# simple_module_tester.net
KiCad netlist of a schematic drawn in EAGLE
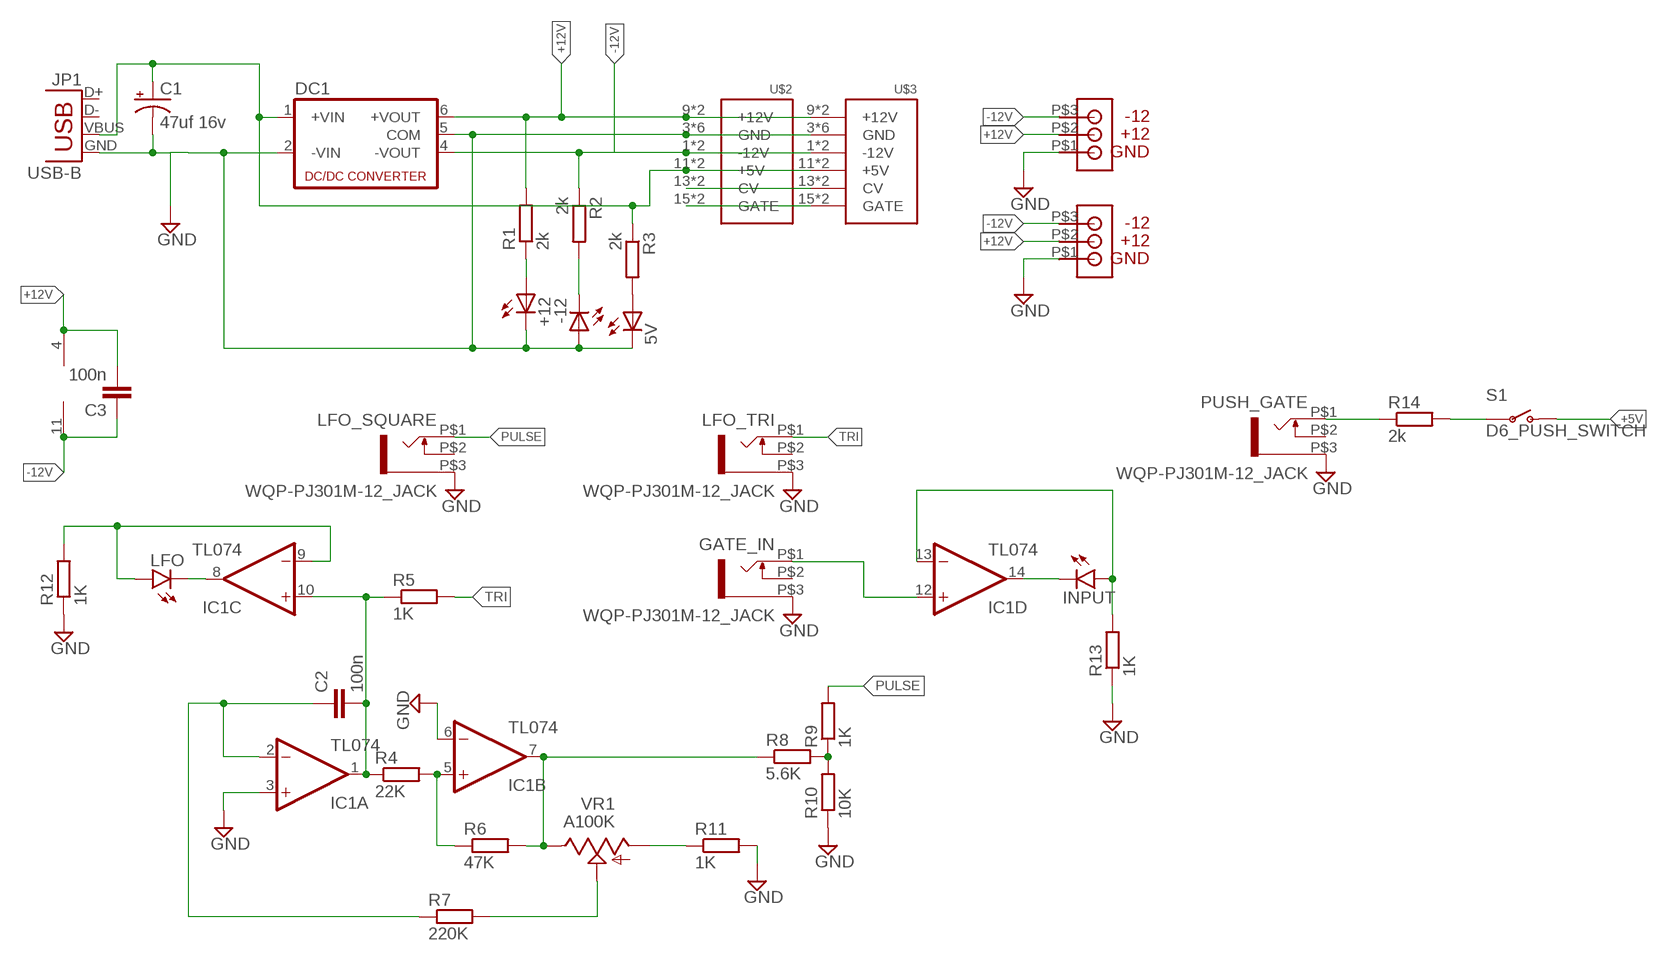
[diagram p0: schematic, sheet 1]

(export (version "E")
  (design (tool "Eeschema 10.0.6"))
  (components
    (comp (ref "+12")
      (value "LED3MM")
      (footprint "eagle-import:LED3MM")
      (libsource (lib "eagle-import") (part "TomW_LED3MM"))
    )
    (comp (ref "-12")
      (value "LED3MM")
      (footprint "eagle-import:LED3MM")
      (libsource (lib "eagle-import") (part "TomW_LED3MM"))
    )
    (comp (ref "5V")
      (value "LED3MM")
      (footprint "eagle-import:LED3MM")
      (libsource (lib "eagle-import") (part "TomW_LED3MM"))
    )
    (comp (ref "C1")
      (value "47uf 16v")
      (footprint "eagle-import:050_020")
      (libsource (lib "eagle-import") (part "050"))
    )
    (comp (ref "C2")
      (value "100n")
      (footprint "eagle-import:AXIAL-5MM")
      (libsource (lib "eagle-import") (part "CAP_"))
    )
    (comp (ref "C3")
      (value "100n")
      (footprint "eagle-import:AXIAL-5MM")
      (libsource (lib "eagle-import") (part "CAP_"))
    )
    (comp (ref "DC1")
      (value "NMA")
      (footprint "eagle-import:NMA")
      (fields (field (name "MF") "C & D TECHNOLOGIES, INC") (field (name "MPN") "NMA0515SC"))
      (libsource (lib "eagle-import") (part "NMA"))
    )
    (comp (ref "GATE_IN")
      (value "WQP-PJ301M-12_JACK")
      (footprint "eagle-import:WQP-PJ301M-12_JACK")
      (libsource (lib "eagle-import") (part "WQP-PJ301M-12_JACK"))
    )
    (comp (ref "IC1")
      (value "TL074")
      (footprint "eagle-import:DIL14")
      (libsource (lib "eagle-import") (part "TL074_"))
    )
    (comp (ref "INPUT")
      (value "LED5MM")
      (footprint "eagle-import:LED5MM")
      (libsource (lib "eagle-import") (part "LED5MM"))
    )
    (comp (ref "JP1")
      (value "USB-B")
      (footprint "eagle-import:USB-B-PTH")
      (libsource (lib "eagle-import") (part "USBPTH"))
    )
    (comp (ref "LFO")
      (value "LED5MM")
      (footprint "eagle-import:LED5MM")
      (libsource (lib "eagle-import") (part "LED5MM"))
    )
    (comp (ref "LFO_SQUARE")
      (value "WQP-PJ301M-12_JACK")
      (footprint "eagle-import:WQP-PJ301M-12_JACK")
      (libsource (lib "eagle-import") (part "WQP-PJ301M-12_JACK"))
    )
    (comp (ref "LFO_TRI")
      (value "WQP-PJ301M-12_JACK")
      (footprint "eagle-import:WQP-PJ301M-12_JACK")
      (libsource (lib "eagle-import") (part "WQP-PJ301M-12_JACK"))
    )
    (comp (ref "PUSH_GATE")
      (value "WQP-PJ301M-12_JACK")
      (footprint "eagle-import:WQP-PJ301M-12_JACK")
      (libsource (lib "eagle-import") (part "WQP-PJ301M-12_JACK"))
    )
    (comp (ref "R1")
      (value "2k")
      (footprint "eagle-import:7MM_RESISTOR")
      (libsource (lib "eagle-import") (part "RESISTOR7MM"))
    )
    (comp (ref "R2")
      (value "2k")
      (footprint "eagle-import:7MM_RESISTOR")
      (libsource (lib "eagle-import") (part "RESISTOR7MM"))
    )
    (comp (ref "R3")
      (value "2k")
      (footprint "eagle-import:7MM_RESISTOR")
      (libsource (lib "eagle-import") (part "RESISTOR7MM"))
    )
    (comp (ref "R4")
      (value "22K")
      (footprint "eagle-import:7MM_RESISTOR")
      (libsource (lib "eagle-import") (part "RESISTOR7MM"))
    )
    (comp (ref "R5")
      (value "1K")
      (footprint "eagle-import:7MM_RESISTOR")
      (libsource (lib "eagle-import") (part "RESISTOR7MM"))
    )
    (comp (ref "R6")
      (value "47K")
      (footprint "eagle-import:7MM_RESISTOR")
      (libsource (lib "eagle-import") (part "RESISTOR7MM"))
    )
    (comp (ref "R7")
      (value "220K")
      (footprint "eagle-import:7MM_RESISTOR")
      (libsource (lib "eagle-import") (part "RESISTOR7MM"))
    )
    (comp (ref "R8")
      (value "5.6K")
      (footprint "eagle-import:7MM_RESISTOR")
      (libsource (lib "eagle-import") (part "RESISTOR7MM"))
    )
    (comp (ref "R9")
      (value "1K")
      (footprint "eagle-import:7MM_RESISTOR")
      (libsource (lib "eagle-import") (part "RESISTOR7MM"))
    )
    (comp (ref "R10")
      (value "10K")
      (footprint "eagle-import:7MM_RESISTOR")
      (libsource (lib "eagle-import") (part "RESISTOR7MM"))
    )
    (comp (ref "R11")
      (value "1K")
      (footprint "eagle-import:7MM_RESISTOR")
      (libsource (lib "eagle-import") (part "RESISTOR7MM"))
    )
    (comp (ref "R12")
      (value "1K")
      (footprint "eagle-import:7MM_RESISTOR")
      (libsource (lib "eagle-import") (part "RESISTOR7MM"))
    )
    (comp (ref "R13")
      (value "1K")
      (footprint "eagle-import:7MM_RESISTOR")
      (libsource (lib "eagle-import") (part "RESISTOR7MM"))
    )
    (comp (ref "R14")
      (value "2k")
      (footprint "eagle-import:7MM_RESISTOR")
      (libsource (lib "eagle-import") (part "RESISTOR7MM"))
    )
    (comp (ref "S1")
      (value "D6_PUSH_SWITCH")
      (footprint "eagle-import:D6_PUSH_SWITCH")
      (libsource (lib "eagle-import") (part "D6_PUSH_SWITCH"))
    )
    (comp (ref "U$1")
      (value "TILE_POWER_WIDE")
      (footprint "eagle-import:THREEPAD_WIDE")
      (libsource (lib "eagle-import") (part "TILE_POWER_WIDE"))
    )
    (comp (ref "U$2")
      (value "POWER")
      (footprint "eagle-import:POWER_16")
      (libsource (lib "eagle-import") (part "POWER"))
    )
    (comp (ref "U$3")
      (value "POWER")
      (footprint "eagle-import:POWER_16")
      (libsource (lib "eagle-import") (part "POWER"))
    )
    (comp (ref "U$4")
      (value "TILE_POWER_WIDE")
      (footprint "eagle-import:THREEPAD_WIDE")
      (libsource (lib "eagle-import") (part "TILE_POWER_WIDE"))
    )
    (comp (ref "VR1")
      (value "A100K")
      (footprint "eagle-import:9MM_SNAP-IN_POT")
      (libsource (lib "eagle-import") (part "9MM_SNAP-IN_POT_"))
    )
  )
  (nets
    (net (code "1") (name "+5V") (class "Default")
      (node (ref "C1") (pin "+") (pinfunction "+_+") (pintype "passive"))
      (node (ref "DC1") (pin "1") (pinfunction "+VIN_1") (pintype "passive"))
      (node (ref "JP1") (pin "VBUS") (pinfunction "VBUS_VBUS") (pintype "bidirectional"))
      (node (ref "R3") (pin "1") (pinfunction "1_1") (pintype "passive"))
      (node (ref "S1") (pin "P$1") (pinfunction "O_P$1") (pintype "passive"))
      (node (ref "S1") (pin "P$2") (pinfunction "O_P$2") (pintype "passive"))
      (node (ref "U$2") (pin "11") (pinfunction "+5V_11") (pintype "bidirectional"))
      (node (ref "U$2") (pin "12") (pinfunction "+5V_12") (pintype "bidirectional"))
      (node (ref "U$3") (pin "11") (pinfunction "+5V_11") (pintype "bidirectional"))
      (node (ref "U$3") (pin "12") (pinfunction "+5V_12") (pintype "bidirectional"))
    )
    (net (code "2") (name "+12V") (class "Default")
      (node (ref "C3") (pin "P$2") (pinfunction "2_P$2") (pintype "passive"))
      (node (ref "DC1") (pin "6") (pinfunction "+VOUT_6") (pintype "passive"))
      (node (ref "IC1") (pin "4") (pinfunction "V+_4") (pintype "power_in"))
      (node (ref "R1") (pin "2") (pinfunction "2_2") (pintype "passive"))
      (node (ref "U$1") (pin "P$2") (pinfunction "P$2_P$2") (pintype "bidirectional"))
      (node (ref "U$2") (pin "10") (pinfunction "+12V_10") (pintype "bidirectional"))
      (node (ref "U$2") (pin "9") (pinfunction "+12V_9") (pintype "bidirectional"))
      (node (ref "U$3") (pin "10") (pinfunction "+12V_10") (pintype "bidirectional"))
      (node (ref "U$3") (pin "9") (pinfunction "+12V_9") (pintype "bidirectional"))
      (node (ref "U$4") (pin "P$2") (pinfunction "P$2_P$2") (pintype "bidirectional"))
    )
    (net (code "3") (name "-12V") (class "Default")
      (node (ref "C3") (pin "P$1") (pinfunction "1_P$1") (pintype "passive"))
      (node (ref "DC1") (pin "4") (pinfunction "-VOUT_4") (pintype "passive"))
      (node (ref "IC1") (pin "11") (pinfunction "V-_11") (pintype "power_in"))
      (node (ref "R2") (pin "1") (pinfunction "1_1") (pintype "passive"))
      (node (ref "U$1") (pin "P$3") (pinfunction "P$3_P$3") (pintype "bidirectional"))
      (node (ref "U$2") (pin "1") (pinfunction "-12V_1") (pintype "bidirectional"))
      (node (ref "U$2") (pin "2") (pinfunction "-12V_2") (pintype "bidirectional"))
      (node (ref "U$3") (pin "1") (pinfunction "-12V_1") (pintype "bidirectional"))
      (node (ref "U$3") (pin "2") (pinfunction "-12V_2") (pintype "bidirectional"))
      (node (ref "U$4") (pin "P$3") (pinfunction "P$3_P$3") (pintype "bidirectional"))
    )
    (net (code "4") (name "GND") (class "Default")
      (node (ref "+12") (pin "K") (pinfunction "C_K") (pintype "passive"))
      (node (ref "-12") (pin "A") (pinfunction "A_A") (pintype "passive"))
      (node (ref "5V") (pin "K") (pinfunction "C_K") (pintype "passive"))
      (node (ref "C1") (pin "-") (pinfunction "-_-") (pintype "passive"))
      (node (ref "DC1") (pin "2") (pinfunction "-VIN_2") (pintype "passive"))
      (node (ref "DC1") (pin "5") (pinfunction "COM_5") (pintype "passive"))
      (node (ref "GATE_IN") (pin "P$3") (pinfunction "1_P$3") (pintype "passive"))
      (node (ref "IC1") (pin "3") (pinfunction "+IN_3") (pintype "input"))
      (node (ref "IC1") (pin "6") (pinfunction "-IN_6") (pintype "input"))
      (node (ref "JP1") (pin "GND") (pinfunction "GND_GND") (pintype "bidirectional"))
      (node (ref "LFO_SQUARE") (pin "P$3") (pinfunction "1_P$3") (pintype "passive"))
      (node (ref "LFO_TRI") (pin "P$3") (pinfunction "1_P$3") (pintype "passive"))
      (node (ref "PUSH_GATE") (pin "P$3") (pinfunction "1_P$3") (pintype "passive"))
      (node (ref "R10") (pin "1") (pinfunction "1_1") (pintype "passive"))
      (node (ref "R11") (pin "2") (pinfunction "2_2") (pintype "passive"))
      (node (ref "R12") (pin "1") (pinfunction "1_1") (pintype "passive"))
      (node (ref "R13") (pin "1") (pinfunction "1_1") (pintype "passive"))
      (node (ref "U$1") (pin "P$1") (pinfunction "P$1_P$1") (pintype "bidirectional"))
      (node (ref "U$2") (pin "3") (pinfunction "GND_3") (pintype "bidirectional"))
      (node (ref "U$2") (pin "4") (pinfunction "GND_4") (pintype "bidirectional"))
      (node (ref "U$2") (pin "5") (pinfunction "GND_5") (pintype "bidirectional"))
      (node (ref "U$2") (pin "6") (pinfunction "GND_6") (pintype "bidirectional"))
      (node (ref "U$2") (pin "7") (pinfunction "GND_7") (pintype "bidirectional"))
      (node (ref "U$2") (pin "8") (pinfunction "GND_8") (pintype "bidirectional"))
      (node (ref "U$3") (pin "3") (pinfunction "GND_3") (pintype "bidirectional"))
      (node (ref "U$3") (pin "4") (pinfunction "GND_4") (pintype "bidirectional"))
      (node (ref "U$3") (pin "5") (pinfunction "GND_5") (pintype "bidirectional"))
      (node (ref "U$3") (pin "6") (pinfunction "GND_6") (pintype "bidirectional"))
      (node (ref "U$3") (pin "7") (pinfunction "GND_7") (pintype "bidirectional"))
      (node (ref "U$3") (pin "8") (pinfunction "GND_8") (pintype "bidirectional"))
      (node (ref "U$4") (pin "P$1") (pinfunction "P$1_P$1") (pintype "bidirectional"))
    )
    (net (code "5") (name "Net-(+12-PadA)") (class "Default")
      (node (ref "+12") (pin "A") (pinfunction "A_A") (pintype "passive"))
      (node (ref "R1") (pin "1") (pinfunction "1_1") (pintype "passive"))
    )
    (net (code "6") (name "Net-(-12-C)") (class "Default")
      (node (ref "-12") (pin "K") (pinfunction "C_K") (pintype "passive"))
      (node (ref "R2") (pin "2") (pinfunction "2_2") (pintype "passive"))
    )
    (net (code "7") (name "Net-(5V-PadA)") (class "Default")
      (node (ref "5V") (pin "A") (pinfunction "A_A") (pintype "passive"))
      (node (ref "R3") (pin "2") (pinfunction "2_2") (pintype "passive"))
    )
    (net (code "8") (name "Net-(C2-1)") (class "Default")
      (node (ref "C2") (pin "P$1") (pinfunction "1_P$1") (pintype "passive"))
      (node (ref "IC1") (pin "2") (pinfunction "-IN_2") (pintype "input"))
      (node (ref "R7") (pin "1") (pinfunction "1_1") (pintype "passive"))
    )
    (net (code "9") (name "Net-(C2-2)") (class "Default")
      (node (ref "C2") (pin "P$2") (pinfunction "2_P$2") (pintype "passive"))
      (node (ref "IC1") (pin "1") (pinfunction "OUT_1") (pintype "output"))
      (node (ref "IC1") (pin "10") (pinfunction "+IN_10") (pintype "input"))
      (node (ref "R4") (pin "1") (pinfunction "1_1") (pintype "passive"))
      (node (ref "R5") (pin "1") (pinfunction "1_1") (pintype "passive"))
    )
    (net (code "10") (name "Net-(GATE_IN-2)") (class "Default")
      (node (ref "GATE_IN") (pin "P$1") (pinfunction "2_P$1") (pintype "passive"))
      (node (ref "IC1") (pin "12") (pinfunction "+IN_12") (pintype "input"))
    )
    (net (code "11") (name "Net-(IC1B-+IN)") (class "Default")
      (node (ref "IC1") (pin "5") (pinfunction "+IN_5") (pintype "input"))
      (node (ref "R4") (pin "2") (pinfunction "2_2") (pintype "passive"))
      (node (ref "R6") (pin "1") (pinfunction "1_1") (pintype "passive"))
    )
    (net (code "12") (name "Net-(IC1B-OUT)") (class "Default")
      (node (ref "IC1") (pin "7") (pinfunction "OUT_7") (pintype "output"))
      (node (ref "R6") (pin "2") (pinfunction "2_2") (pintype "passive"))
      (node (ref "R8") (pin "1") (pinfunction "1_1") (pintype "passive"))
      (node (ref "VR1") (pin "3") (pinfunction "E_3") (pintype "passive"))
    )
    (net (code "13") (name "Net-(IC1C--IN)") (class "Default")
      (node (ref "IC1") (pin "9") (pinfunction "-IN_9") (pintype "input"))
      (node (ref "LFO") (pin "A") (pinfunction "A_A") (pintype "passive"))
      (node (ref "R12") (pin "2") (pinfunction "2_2") (pintype "passive"))
    )
    (net (code "14") (name "Net-(IC1C-OUT)") (class "Default")
      (node (ref "IC1") (pin "8") (pinfunction "OUT_8") (pintype "output"))
      (node (ref "LFO") (pin "K") (pinfunction "C_K") (pintype "passive"))
    )
    (net (code "15") (name "Net-(IC1D--IN)") (class "Default")
      (node (ref "IC1") (pin "13") (pinfunction "-IN_13") (pintype "input"))
      (node (ref "INPUT") (pin "A") (pinfunction "A_A") (pintype "passive"))
      (node (ref "R13") (pin "2") (pinfunction "2_2") (pintype "passive"))
    )
    (net (code "16") (name "Net-(IC1D-OUT)") (class "Default")
      (node (ref "IC1") (pin "14") (pinfunction "OUT_14") (pintype "output"))
      (node (ref "INPUT") (pin "K") (pinfunction "C_K") (pintype "passive"))
    )
    (net (code "17") (name "Net-(PUSH_GATE-2)") (class "Default")
      (node (ref "PUSH_GATE") (pin "P$1") (pinfunction "2_P$1") (pintype "passive"))
      (node (ref "R14") (pin "1") (pinfunction "1_1") (pintype "passive"))
    )
    (net (code "18") (name "Net-(R10-Pad2)") (class "Default")
      (node (ref "R10") (pin "2") (pinfunction "2_2") (pintype "passive"))
      (node (ref "R8") (pin "2") (pinfunction "2_2") (pintype "passive"))
      (node (ref "R9") (pin "1") (pinfunction "1_1") (pintype "passive"))
    )
    (net (code "19") (name "Net-(R14-Pad2)") (class "Default")
      (node (ref "R14") (pin "2") (pinfunction "2_2") (pintype "passive"))
      (node (ref "S1") (pin "P$3") (pinfunction "P_P$3") (pintype "passive"))
      (node (ref "S1") (pin "P$4") (pinfunction "P_P$4") (pintype "passive"))
    )
    (net (code "20") (name "Net-(U$2-CV-Pad13)") (class "Default")
      (node (ref "U$2") (pin "13") (pinfunction "CV_13") (pintype "bidirectional"))
      (node (ref "U$2") (pin "14") (pinfunction "CV_14") (pintype "bidirectional"))
      (node (ref "U$3") (pin "13") (pinfunction "CV_13") (pintype "bidirectional"))
      (node (ref "U$3") (pin "14") (pinfunction "CV_14") (pintype "bidirectional"))
    )
    (net (code "21") (name "Net-(U$2-GATE-Pad15)") (class "Default")
      (node (ref "U$2") (pin "15") (pinfunction "GATE_15") (pintype "bidirectional"))
      (node (ref "U$2") (pin "16") (pinfunction "GATE_16") (pintype "bidirectional"))
      (node (ref "U$3") (pin "15") (pinfunction "GATE_15") (pintype "bidirectional"))
      (node (ref "U$3") (pin "16") (pinfunction "GATE_16") (pintype "bidirectional"))
    )
    (net (code "22") (name "Net-(VR1-A)") (class "Default")
      (node (ref "R11") (pin "1") (pinfunction "1_1") (pintype "passive"))
      (node (ref "VR1") (pin "1") (pinfunction "A_1") (pintype "passive"))
    )
    (net (code "23") (name "Net-(VR1-S)") (class "Default")
      (node (ref "R7") (pin "2") (pinfunction "2_2") (pintype "passive"))
      (node (ref "VR1") (pin "2") (pinfunction "S_2") (pintype "passive"))
    )
    (net (code "24") (name "PULSE") (class "Default")
      (node (ref "LFO_SQUARE") (pin "P$1") (pinfunction "2_P$1") (pintype "passive"))
      (node (ref "R9") (pin "2") (pinfunction "2_2") (pintype "passive"))
    )
    (net (code "25") (name "TRI") (class "Default")
      (node (ref "LFO_TRI") (pin "P$1") (pinfunction "2_P$1") (pintype "passive"))
      (node (ref "R5") (pin "2") (pinfunction "2_2") (pintype "passive"))
    )
    (net (code "26") (name "unconnected-(GATE_IN-3-PadP$2)") (class "Default")
      (node (ref "GATE_IN") (pin "P$2") (pinfunction "3_P$2") (pintype "passive"))
    )
    (net (code "27") (name "unconnected-(JP1-PadD+)") (class "Default")
      (node (ref "JP1") (pin "D+") (pinfunction "D+_D+") (pintype "bidirectional"))
    )
    (net (code "28") (name "unconnected-(JP1-PadD-)") (class "Default")
      (node (ref "JP1") (pin "D-") (pinfunction "D-_D-") (pintype "bidirectional"))
    )
    (net (code "29") (name "unconnected-(LFO_SQUARE-3-PadP$2)") (class "Default")
      (node (ref "LFO_SQUARE") (pin "P$2") (pinfunction "3_P$2") (pintype "passive"))
    )
    (net (code "30") (name "unconnected-(LFO_TRI-3-PadP$2)") (class "Default")
      (node (ref "LFO_TRI") (pin "P$2") (pinfunction "3_P$2") (pintype "passive"))
    )
    (net (code "31") (name "unconnected-(PUSH_GATE-3-PadP$2)") (class "Default")
      (node (ref "PUSH_GATE") (pin "P$2") (pinfunction "3_P$2") (pintype "passive"))
    )
  )
)
